# etna-main-pmic.net
KiCad netlist of a schematic drawn in Altium Designer
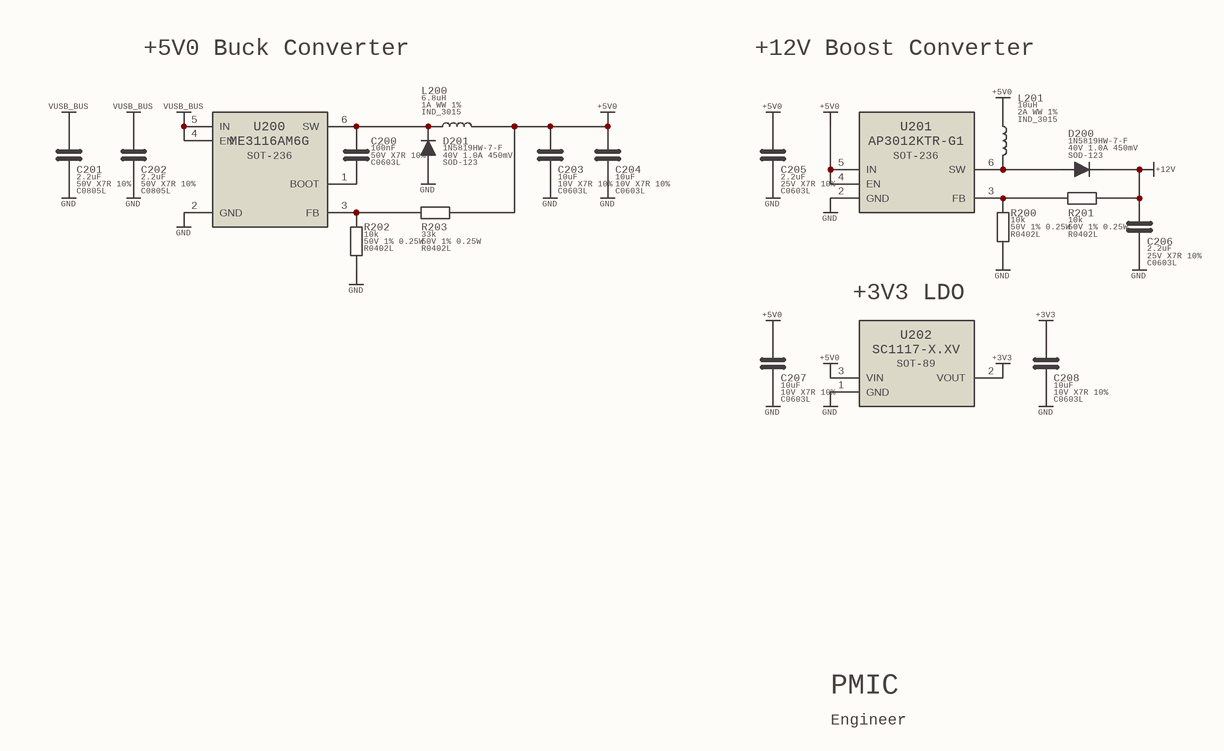
[diagram p0: etna-main-pmic.SchDoc]

(export (version "E")
  (design (tool "Eeschema 10.0.6"))
  (components
    (comp (ref "C200")
      (value "100nF")
      (footprint "C0603L")
      (fields (field (name "SPECIFICATION") "50V X7R 10%") (field (name "Comment") "100n"))
      (libsource (lib "discreet") (part "CAPACITOR_NONPOL"))
    )
    (comp (ref "C201")
      (value "2.2uF")
      (footprint "C0805L")
      (fields (field (name "SPECIFICATION") "50V X7R 10%") (field (name "Comment") "100n"))
      (libsource (lib "discreet") (part "CAPACITOR_NONPOL"))
    )
    (comp (ref "C202")
      (value "2.2uF")
      (footprint "C0805L")
      (fields (field (name "SPECIFICATION") "50V X7R 10%") (field (name "Comment") "100n"))
      (libsource (lib "discreet") (part "CAPACITOR_NONPOL"))
    )
    (comp (ref "C203")
      (value "10uF")
      (footprint "C0603L")
      (fields (field (name "SPECIFICATION") "10V X7R 10%") (field (name "Comment") "100n"))
      (libsource (lib "discreet") (part "CAPACITOR_NONPOL"))
    )
    (comp (ref "C204")
      (value "10uF")
      (footprint "C0603L")
      (fields (field (name "SPECIFICATION") "10V X7R 10%") (field (name "Comment") "100n"))
      (libsource (lib "discreet") (part "CAPACITOR_NONPOL"))
    )
    (comp (ref "C205")
      (value "2.2uF")
      (footprint "C0603L")
      (fields (field (name "SPECIFICATION") "25V X7R 10%") (field (name "Comment") "100n"))
      (libsource (lib "discreet") (part "CAPACITOR_NONPOL"))
    )
    (comp (ref "C206")
      (value "2.2uF")
      (footprint "C0603L")
      (fields (field (name "SPECIFICATION") "25V X7R 10%") (field (name "Comment") "100n"))
      (libsource (lib "discreet") (part "CAPACITOR_NONPOL"))
    )
    (comp (ref "C207")
      (value "10uF")
      (footprint "C0603L")
      (fields (field (name "SPECIFICATION") "10V X7R 10%") (field (name "Comment") "100n"))
      (libsource (lib "discreet") (part "CAPACITOR_NONPOL"))
    )
    (comp (ref "C208")
      (value "10uF")
      (footprint "C0603L")
      (fields (field (name "SPECIFICATION") "10V X7R 10%") (field (name "Comment") "100n"))
      (libsource (lib "discreet") (part "CAPACITOR_NONPOL"))
    )
    (comp (ref "D200")
      (value "1N5819HW-7-F")
      (footprint "SOD-123")
      (fields (field (name "SPECIFICATION") "40V 1.0A 450mV") (field (name "Comment") "DIODE"))
      (libsource (lib "discreet") (part "DIODE"))
    )
    (comp (ref "D201")
      (value "1N5819HW-7-F")
      (footprint "SOD-123")
      (fields (field (name "SPECIFICATION") "40V 1.0A 450mV") (field (name "Comment") "DIODE"))
      (libsource (lib "discreet") (part "DIODE"))
    )
    (comp (ref "L200")
      (value "6.8uH")
      (footprint "IND_3015")
      (fields (field (name "SPECIFICATION") "1A WW 1%") (field (name "Comment") "INDUCTOR"))
      (libsource (lib "discreet") (part "INDUCTOR"))
    )
    (comp (ref "L201")
      (value "10uH")
      (footprint "IND_3015")
      (fields (field (name "SPECIFICATION") "2A WW 1%") (field (name "Comment") "INDUCTOR"))
      (libsource (lib "discreet") (part "INDUCTOR"))
    )
    (comp (ref "R200")
      (value "10k")
      (footprint "R0402L")
      (fields (field (name "SPECIFICATION") "50V 1% 0.25W"))
      (libsource (lib "passive") (part "RESISTOR"))
    )
    (comp (ref "R201")
      (value "10k")
      (footprint "R0402L")
      (fields (field (name "SPECIFICATION") "50V 1% 0.25W"))
      (libsource (lib "") (part "RESISTOR_1"))
    )
    (comp (ref "R202")
      (value "10k")
      (footprint "R0402L")
      (fields (field (name "SPECIFICATION") "50V 1% 0.25W"))
      (libsource (lib "passive") (part "RESISTOR"))
    )
    (comp (ref "R203")
      (value "33k")
      (footprint "R0402L")
      (fields (field (name "SPECIFICATION") "50V 1% 0.25W"))
      (libsource (lib "") (part "RESISTOR_2"))
    )
    (comp (ref "U200")
      (value "ME3116AM6G")
      (footprint "SOT-236")
      (description "LMR14006")
      (libsource (lib "ic") (part "LMR14006"))
    )
    (comp (ref "U201")
      (value "AP3012KTR-G1")
      (footprint "SOT-236")
      (libsource (lib "ic") (part "AP3012KTR-G1"))
    )
    (comp (ref "U202") (value "SC1117-X.XV") (footprint "SOT-89") (libsource (lib "ic") (part "SC1117-X.XV")))
  )
  (nets
    (net (code "1") (name "+3V3") (class "Default")
      (node (ref "C208") (pin "1") (pinfunction "1_1") (pintype "passive"))
      (node (ref "U202") (pin "2") (pinfunction "VOUT_2") (pintype "passive"))
    )
    (net (code "2") (name "+5V0") (class "Default")
      (node (ref "C203") (pin "1") (pinfunction "1_1") (pintype "passive"))
      (node (ref "C204") (pin "1") (pinfunction "1_1") (pintype "passive"))
      (node (ref "C205") (pin "1") (pinfunction "1_1") (pintype "passive"))
      (node (ref "C207") (pin "1") (pinfunction "1_1") (pintype "passive"))
      (node (ref "L200") (pin "2") (pintype "passive"))
      (node (ref "L201") (pin "1") (pintype "passive"))
      (node (ref "R203") (pin "1") (pinfunction "1_1") (pintype "passive"))
      (node (ref "U201") (pin "4") (pinfunction "EN_4") (pintype "passive"))
      (node (ref "U201") (pin "5") (pinfunction "IN_5") (pintype "passive"))
      (node (ref "U202") (pin "3") (pinfunction "VIN_3") (pintype "passive"))
    )
    (net (code "3") (name "+12V") (class "Default")
      (node (ref "C206") (pin "1") (pinfunction "1_1") (pintype "passive"))
      (node (ref "D200") (pin "2") (pinfunction "K_2") (pintype "passive"))
      (node (ref "R201") (pin "2") (pinfunction "2_2") (pintype "passive"))
    )
    (net (code "4") (name "GND") (class "Default")
      (node (ref "C201") (pin "2") (pinfunction "2_2") (pintype "passive"))
      (node (ref "C202") (pin "2") (pinfunction "2_2") (pintype "passive"))
      (node (ref "C203") (pin "2") (pinfunction "2_2") (pintype "passive"))
      (node (ref "C204") (pin "2") (pinfunction "2_2") (pintype "passive"))
      (node (ref "C205") (pin "2") (pinfunction "2_2") (pintype "passive"))
      (node (ref "C206") (pin "2") (pinfunction "2_2") (pintype "passive"))
      (node (ref "C207") (pin "2") (pinfunction "2_2") (pintype "passive"))
      (node (ref "C208") (pin "2") (pinfunction "2_2") (pintype "passive"))
      (node (ref "D201") (pin "1") (pinfunction "A_1") (pintype "passive"))
      (node (ref "R200") (pin "2") (pinfunction "2_2") (pintype "passive"))
      (node (ref "R202") (pin "2") (pinfunction "2_2") (pintype "passive"))
      (node (ref "U200") (pin "2") (pinfunction "GND_2") (pintype "passive"))
      (node (ref "U201") (pin "2") (pinfunction "GND_2") (pintype "passive"))
      (node (ref "U202") (pin "1") (pinfunction "GND_1") (pintype "passive"))
    )
    (net (code "5") (name "Net-(D200-A)") (class "Default")
      (node (ref "D200") (pin "1") (pinfunction "A_1") (pintype "passive"))
      (node (ref "L201") (pin "2") (pintype "passive"))
      (node (ref "U201") (pin "6") (pinfunction "SW_6") (pintype "passive"))
    )
    (net (code "6") (name "Net-(D201-K)") (class "Default")
      (node (ref "C200") (pin "1") (pinfunction "1_1") (pintype "passive"))
      (node (ref "D201") (pin "2") (pinfunction "K_2") (pintype "passive"))
      (node (ref "L200") (pin "1") (pintype "passive"))
      (node (ref "U200") (pin "6") (pinfunction "SW_6") (pintype "passive"))
    )
    (net (code "7") (name "Net-(U200-BOOT)") (class "Default")
      (node (ref "C200") (pin "2") (pinfunction "2_2") (pintype "passive"))
      (node (ref "U200") (pin "1") (pinfunction "BOOT_1") (pintype "passive"))
    )
    (net (code "8") (name "Net-(U200-FB)") (class "Default")
      (node (ref "R202") (pin "1") (pinfunction "1_1") (pintype "passive"))
      (node (ref "R203") (pin "2") (pinfunction "2_2") (pintype "passive"))
      (node (ref "U200") (pin "3") (pinfunction "FB_3") (pintype "passive"))
    )
    (net (code "9") (name "Net-(U201-FB)") (class "Default")
      (node (ref "R200") (pin "1") (pinfunction "1_1") (pintype "passive"))
      (node (ref "R201") (pin "1") (pinfunction "1_1") (pintype "passive"))
      (node (ref "U201") (pin "3") (pinfunction "FB_3") (pintype "passive"))
    )
    (net (code "10") (name "VUSB_BUS") (class "Default")
      (node (ref "C201") (pin "1") (pinfunction "1_1") (pintype "passive"))
      (node (ref "C202") (pin "1") (pinfunction "1_1") (pintype "passive"))
      (node (ref "U200") (pin "4") (pinfunction "EN_4") (pintype "passive"))
      (node (ref "U200") (pin "5") (pinfunction "IN_5") (pintype "passive"))
    )
    (net (code "11") (name "unconnected-(U200-N.C.-Pad44)") (class "Default")
      (node (ref "U200") (pin "44") (pinfunction "N.C._44") (pintype "passive"))
    )
    (net (code "12") (name "unconnected-(U201-N.C.-Pad44)") (class "Default")
      (node (ref "U201") (pin "44") (pinfunction "N.C._44") (pintype "passive"))
    )
    (net (code "13") (name "unconnected-(U202-N.C.-Pad44)") (class "Default")
      (node (ref "U202") (pin "44") (pinfunction "N.C._44") (pintype "passive"))
    )
  )
)
